# 2020.net
KiCad netlist of a schematic drawn in Altium Designer
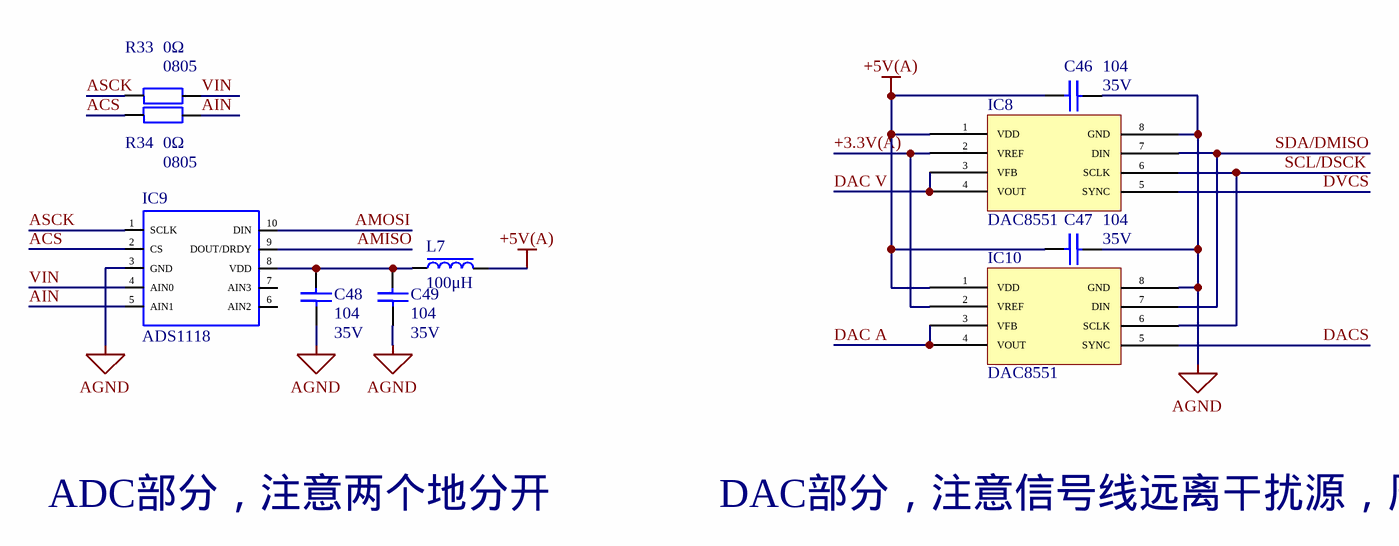
[diagram p0: 2020年电赛校赛测量、基准板.SchDoc]

(export (version "E")
  (design (tool "Eeschema 10.0.6"))
  (components
    (comp (ref "C46")
      (value "104")
      (footprint "C0805")
      (description "无极性电容")
      (fields (field (name "ALTIUM_VALUE") "35V"))
      (libsource (lib "原理图库") (part "104"))
    )
    (comp (ref "C47")
      (value "104")
      (footprint "C0805")
      (description "无极性电容")
      (fields (field (name "ALTIUM_VALUE") "35V"))
      (libsource (lib "原理图库") (part "104"))
    )
    (comp (ref "C48")
      (value "104")
      (footprint "C0805")
      (description "无极性电容")
      (fields (field (name "ALTIUM_VALUE") "35V"))
      (libsource (lib "原理图库") (part "104"))
    )
    (comp (ref "C49")
      (value "104")
      (footprint "C0805")
      (description "无极性电容")
      (fields (field (name "ALTIUM_VALUE") "35V"))
      (libsource (lib "原理图库") (part "104"))
    )
    (comp (ref "IC8") (value "DAC8551") (footprint "MSOP-8") (libsource (lib "Lib") (part "DAC8551")))
    (comp (ref "IC9")
      (value "ADS1118")
      (footprint "MSOP-10")
      (description "16bit ADC 860SPS 4路单端/两路差分")
      (libsource (lib "原理图库") (part "ADS1118"))
    )
    (comp (ref "IC10") (value "DAC8551") (footprint "MSOP-8") (libsource (lib "Lib") (part "DAC8551")))
    (comp (ref "L7")
      (value "100μH")
      (footprint "R0805")
      (description "电感")
      (libsource (lib "原理图库") (part "470mH"))
    )
    (comp (ref "R33")
      (value "0Ω")
      (footprint "R0805")
      (description "贴片/直插电阻")
      (fields (field (name "ALTIUM_VALUE") "0805"))
      (libsource (lib "原理图库") (part "10kΩ"))
    )
    (comp (ref "R34")
      (value "0Ω")
      (footprint "R0805")
      (description "贴片/直插电阻")
      (fields (field (name "ALTIUM_VALUE") "0805"))
      (libsource (lib "原理图库") (part "10kΩ"))
    )
  )
  (nets
    (net (code "1") (name "+5V(A)") (class "Default")
      (node (ref "C46") (pin "1") (pintype "passive"))
      (node (ref "C47") (pin "1") (pintype "passive"))
      (node (ref "IC10") (pin "1") (pinfunction "VDD_1") (pintype "passive"))
      (node (ref "IC8") (pin "1") (pinfunction "VDD_1") (pintype "passive"))
      (node (ref "L7") (pin "1") (pintype "passive"))
    )
    (net (code "2") (name "/+3.3V(A)") (class "Default")
      (node (ref "IC10") (pin "2") (pinfunction "VREF_2") (pintype "passive"))
      (node (ref "IC8") (pin "2") (pinfunction "VREF_2") (pintype "passive"))
    )
    (net (code "3") (name "/ACS") (class "Default")
      (node (ref "IC9") (pin "2") (pinfunction "CS_2") (pintype "passive"))
      (node (ref "R34") (pin "1") (pintype "passive"))
    )
    (net (code "4") (name "/AIN") (class "Default")
      (node (ref "IC9") (pin "5") (pinfunction "AIN1_5") (pintype "passive"))
      (node (ref "R34") (pin "2") (pintype "passive"))
    )
    (net (code "5") (name "/AMISO") (class "Default")
      (node (ref "IC9") (pin "9") (pinfunction "DOUT/DRDY_9") (pintype "passive"))
    )
    (net (code "6") (name "/AMOSI") (class "Default")
      (node (ref "IC9") (pin "10") (pinfunction "DIN_10") (pintype "passive"))
    )
    (net (code "7") (name "/ASCK") (class "Default")
      (node (ref "IC9") (pin "1") (pinfunction "SCLK_1") (pintype "passive"))
      (node (ref "R33") (pin "1") (pintype "passive"))
    )
    (net (code "8") (name "/DAC A") (class "Default")
      (node (ref "IC10") (pin "3") (pinfunction "VFB_3") (pintype "passive"))
      (node (ref "IC10") (pin "4") (pinfunction "VOUT_4") (pintype "passive"))
    )
    (net (code "9") (name "/DAC V") (class "Default")
      (node (ref "IC8") (pin "3") (pinfunction "VFB_3") (pintype "passive"))
      (node (ref "IC8") (pin "4") (pinfunction "VOUT_4") (pintype "passive"))
    )
    (net (code "10") (name "/DACS") (class "Default")
      (node (ref "IC10") (pin "5") (pinfunction "SYNC_5") (pintype "passive"))
    )
    (net (code "11") (name "/DVCS") (class "Default")
      (node (ref "IC8") (pin "5") (pinfunction "SYNC_5") (pintype "passive"))
    )
    (net (code "12") (name "/SCL{slash}DSCK") (class "Default")
      (node (ref "IC10") (pin "6") (pinfunction "SCLK_6") (pintype "passive"))
      (node (ref "IC8") (pin "6") (pinfunction "SCLK_6") (pintype "passive"))
    )
    (net (code "13") (name "/SDA{slash}DMISO") (class "Default")
      (node (ref "IC10") (pin "7") (pinfunction "DIN_7") (pintype "passive"))
      (node (ref "IC8") (pin "7") (pinfunction "DIN_7") (pintype "passive"))
    )
    (net (code "14") (name "/VIN") (class "Default")
      (node (ref "IC9") (pin "4") (pinfunction "AIN0_4") (pintype "passive"))
      (node (ref "R33") (pin "2") (pintype "passive"))
    )
    (net (code "15") (name "AGND") (class "Default")
      (node (ref "C46") (pin "2") (pintype "passive"))
      (node (ref "C47") (pin "2") (pintype "passive"))
      (node (ref "C48") (pin "1") (pintype "passive"))
      (node (ref "C49") (pin "1") (pintype "passive"))
      (node (ref "IC10") (pin "8") (pinfunction "GND_8") (pintype "passive"))
      (node (ref "IC8") (pin "8") (pinfunction "GND_8") (pintype "passive"))
      (node (ref "IC9") (pin "3") (pinfunction "GND_3") (pintype "passive"))
    )
    (net (code "16") (name "Net-(IC9-VDD)") (class "Default")
      (node (ref "C48") (pin "2") (pintype "passive"))
      (node (ref "C49") (pin "2") (pintype "passive"))
      (node (ref "IC9") (pin "8") (pinfunction "VDD_8") (pintype "passive"))
      (node (ref "L7") (pin "2") (pintype "passive"))
    )
    (net (code "17") (name "unconnected-(IC9-AIN2-Pad6)") (class "Default")
      (node (ref "IC9") (pin "6") (pinfunction "AIN2_6") (pintype "passive"))
    )
    (net (code "18") (name "unconnected-(IC9-AIN3-Pad7)") (class "Default")
      (node (ref "IC9") (pin "7") (pinfunction "AIN3_7") (pintype "passive"))
    )
  )
)
